# POS12V.net
KiCad netlist of a schematic drawn in Altium Designer
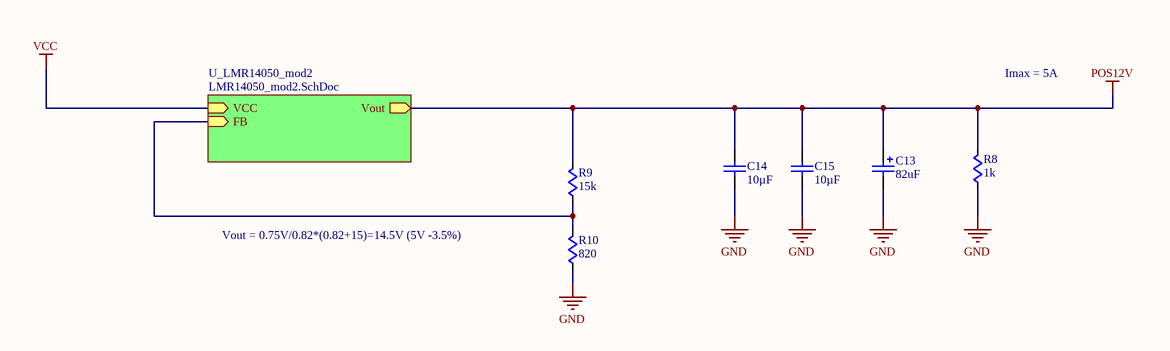
[diagram p0: POS12V.SchDoc]

(export (version "E")
  (design (tool "Eeschema 10.0.6"))
  (components
    (comp (ref "C13")
      (value "82uF")
      (footprint "CAP_EEFK_D8")
      (description "Polarized Capacitor (Surface Mount)")
      (fields (field (name "MANUFACTURER_PART_NUMBER") "EEEFK1V680XP"))
      (libsource (lib "AEVC-lib") (part "EEEFK1V680XP"))
    )
    (comp (ref "C14")
      (value "10µF")
      (footprint "C0805")
      (description "capacitor")
      (fields (field (name "Comment") "Cap"))
      (libsource (lib "ChipComponents") (part "Cap"))
    )
    (comp (ref "C15")
      (value "10µF")
      (footprint "C0805")
      (description "capacitor")
      (fields (field (name "Comment") "Cap"))
      (libsource (lib "ChipComponents") (part "Cap"))
    )
    (comp (ref "R8")
      (value "1k")
      (footprint "R0805")
      (description "resistor")
      (fields (field (name "Comment") "Res"))
      (libsource (lib "ChipComponents") (part "Res"))
    )
    (comp (ref "R9")
      (value "15k")
      (footprint "R0805")
      (description "resistor")
      (fields (field (name "Comment") "Res"))
      (libsource (lib "ChipComponents") (part "Res"))
    )
    (comp (ref "R10")
      (value "820")
      (footprint "R0805")
      (description "resistor")
      (fields (field (name "Comment") "Res"))
      (libsource (lib "ChipComponents") (part "Res"))
    )
  )
  (nets
    (net (code "1") (name "/FB") (class "Default")
      (node (ref "R10") (pin "2") (pinfunction "2_2") (pintype "passive"))
      (node (ref "R9") (pin "1") (pinfunction "1_1") (pintype "passive"))
    )
    (net (code "2") (name "GND") (class "Default")
      (node (ref "C13") (pin "2") (pinfunction "2_2") (pintype "passive"))
      (node (ref "C14") (pin "1") (pinfunction "1_1") (pintype "passive"))
      (node (ref "C15") (pin "1") (pinfunction "1_1") (pintype "passive"))
      (node (ref "R10") (pin "1") (pinfunction "1_1") (pintype "passive"))
      (node (ref "R8") (pin "1") (pinfunction "1_1") (pintype "passive"))
    )
    (net (code "3") (name "POS12V") (class "Default")
      (node (ref "C13") (pin "1") (pinfunction "1_1") (pintype "passive"))
      (node (ref "C14") (pin "2") (pinfunction "2_2") (pintype "passive"))
      (node (ref "C15") (pin "2") (pinfunction "2_2") (pintype "passive"))
      (node (ref "R8") (pin "2") (pinfunction "2_2") (pintype "passive"))
      (node (ref "R9") (pin "2") (pinfunction "2_2") (pintype "passive"))
    )
  )
)
